# fonte4.net
KiCad netlist of a schematic drawn in EAGLE
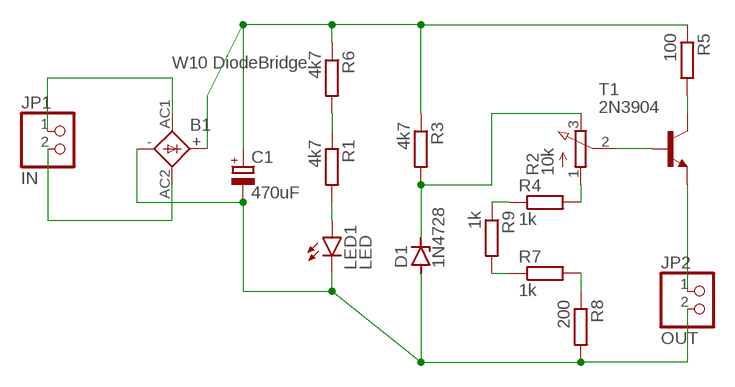
[diagram p0: schematic, sheet 1]

(export (version "E")
  (design (tool "Eeschema 10.0.6"))
  (components
    (comp (ref "B1")
      (value "W10 DiodeBridge")
      (footprint "eagle-import:1KAB")
      (libsource (lib "eagle-import") (part "1KAB"))
    )
    (comp (ref "C1")
      (value "470uF")
      (footprint "eagle-import:E5-10,5")
      (libsource (lib "eagle-import") (part "CPOL-EUE5-10.5"))
    )
    (comp (ref "D1")
      (value "1N4728")
      (footprint "eagle-import:DO41Z10")
      (libsource (lib "eagle-import") (part "1N4728"))
    )
    (comp (ref "JP1")
      (value "IN")
      (footprint "eagle-import:1X02")
      (libsource (lib "eagle-import") (part "PINHD-1X2"))
    )
    (comp (ref "JP2")
      (value "OUT")
      (footprint "eagle-import:1X02")
      (libsource (lib "eagle-import") (part "PINHD-1X2"))
    )
    (comp (ref "LED1")
      (value "LED")
      (footprint "eagle-import:LED5MM")
      (libsource (lib "eagle-import") (part "LED5MM"))
    )
    (comp (ref "R1")
      (value "4k7")
      (footprint "eagle-import:0204_7")
      (libsource (lib "eagle-import") (part "R-EU_0204/7"))
    )
    (comp (ref "R2")
      (value "10k")
      (footprint "eagle-import:3RP_1610N")
      (libsource (lib "eagle-import") (part "3RP/1610N"))
    )
    (comp (ref "R3")
      (value "4k7")
      (footprint "eagle-import:0204_7")
      (libsource (lib "eagle-import") (part "R-EU_0204/7"))
    )
    (comp (ref "R4")
      (value "1k")
      (footprint "eagle-import:0204_7")
      (libsource (lib "eagle-import") (part "R-EU_0204/7"))
    )
    (comp (ref "R5")
      (value "100")
      (footprint "eagle-import:0204_7")
      (libsource (lib "eagle-import") (part "R-EU_0204/7"))
    )
    (comp (ref "R6")
      (value "4k7")
      (footprint "eagle-import:0204_7")
      (libsource (lib "eagle-import") (part "R-EU_0204/7"))
    )
    (comp (ref "R7")
      (value "1k")
      (footprint "eagle-import:0204_7")
      (libsource (lib "eagle-import") (part "R-EU_0204/7"))
    )
    (comp (ref "R8")
      (value "200")
      (footprint "eagle-import:0204_7")
      (libsource (lib "eagle-import") (part "R-EU_0204/7"))
    )
    (comp (ref "R9")
      (value "1k")
      (footprint "eagle-import:0204_7")
      (libsource (lib "eagle-import") (part "R-EU_0204/7"))
    )
    (comp (ref "T1")
      (value "2N3904")
      (footprint "eagle-import:TO92")
      (libsource (lib "eagle-import") (part "2N3904"))
    )
  )
  (nets
    (net (code "1") (name "Net-(B1-Pad+)") (class "Default")
      (node (ref "B1") (pin "+") (pinfunction "+_+") (pintype "passive"))
      (node (ref "C1") (pin "+") (pinfunction "+_+") (pintype "passive"))
      (node (ref "R3") (pin "1") (pinfunction "1_1") (pintype "passive"))
      (node (ref "R5") (pin "1") (pinfunction "1_1") (pintype "passive"))
      (node (ref "R6") (pin "1") (pinfunction "1_1") (pintype "passive"))
    )
    (net (code "2") (name "Net-(B1-PadAC1)") (class "Default")
      (node (ref "B1") (pin "AC1") (pinfunction "AC1_AC1") (pintype "passive"))
      (node (ref "JP1") (pin "1") (pinfunction "1_1") (pintype "passive"))
    )
    (net (code "3") (name "Net-(B1-PadAC2)") (class "Default")
      (node (ref "B1") (pin "AC2") (pinfunction "AC2_AC2") (pintype "passive"))
      (node (ref "JP1") (pin "2") (pinfunction "2_2") (pintype "passive"))
    )
    (net (code "4") (name "Net-(LED1-C)") (class "Default")
      (node (ref "B1") (pin "-") (pinfunction "-_-") (pintype "passive"))
      (node (ref "C1") (pin "-") (pinfunction "-_-") (pintype "passive"))
      (node (ref "D1") (pin "A") (pinfunction "A_A") (pintype "passive"))
      (node (ref "JP2") (pin "2") (pinfunction "2_2") (pintype "passive"))
      (node (ref "LED1") (pin "K") (pinfunction "C_K") (pintype "passive"))
      (node (ref "R8") (pin "2") (pinfunction "2_2") (pintype "passive"))
    )
    (net (code "5") (name "Net-(LED1-PadA)") (class "Default")
      (node (ref "LED1") (pin "A") (pinfunction "A_A") (pintype "passive"))
      (node (ref "R1") (pin "2") (pinfunction "2_2") (pintype "passive"))
    )
    (net (code "6") (name "Net-(R1-Pad1)") (class "Default")
      (node (ref "R1") (pin "1") (pinfunction "1_1") (pintype "passive"))
      (node (ref "R6") (pin "2") (pinfunction "2_2") (pintype "passive"))
    )
    (net (code "7") (name "Net-(R2-A)") (class "Default")
      (node (ref "R2") (pin "1") (pinfunction "A_1") (pintype "passive"))
      (node (ref "R4") (pin "2") (pinfunction "2_2") (pintype "passive"))
    )
    (net (code "8") (name "Net-(R2-E)") (class "Default")
      (node (ref "D1") (pin "C") (pinfunction "C_C") (pintype "passive"))
      (node (ref "R2") (pin "3") (pinfunction "E_3") (pintype "passive"))
      (node (ref "R3") (pin "2") (pinfunction "2_2") (pintype "passive"))
    )
    (net (code "9") (name "Net-(R2-S)") (class "Default")
      (node (ref "R2") (pin "2") (pinfunction "S_2") (pintype "passive"))
      (node (ref "T1") (pin "2") (pinfunction "B_2") (pintype "passive"))
    )
    (net (code "10") (name "Net-(R4-Pad1)") (class "Default")
      (node (ref "R4") (pin "1") (pinfunction "1_1") (pintype "passive"))
      (node (ref "R9") (pin "1") (pinfunction "1_1") (pintype "passive"))
    )
    (net (code "11") (name "Net-(R7-Pad1)") (class "Default")
      (node (ref "R7") (pin "1") (pinfunction "1_1") (pintype "passive"))
      (node (ref "R9") (pin "2") (pinfunction "2_2") (pintype "passive"))
    )
    (net (code "12") (name "Net-(R7-Pad2)") (class "Default")
      (node (ref "R7") (pin "2") (pinfunction "2_2") (pintype "passive"))
      (node (ref "R8") (pin "1") (pinfunction "1_1") (pintype "passive"))
    )
    (net (code "13") (name "Net-(T1-C)") (class "Default")
      (node (ref "R5") (pin "2") (pinfunction "2_2") (pintype "passive"))
      (node (ref "T1") (pin "1") (pinfunction "C_1") (pintype "passive"))
    )
    (net (code "14") (name "Net-(T1-E)") (class "Default")
      (node (ref "JP2") (pin "1") (pinfunction "1_1") (pintype "passive"))
      (node (ref "T1") (pin "3") (pinfunction "E_3") (pintype "passive"))
    )
  )
)
